# 08_USB_OTG_POWER.net
KiCad netlist of a schematic drawn in Altium Designer
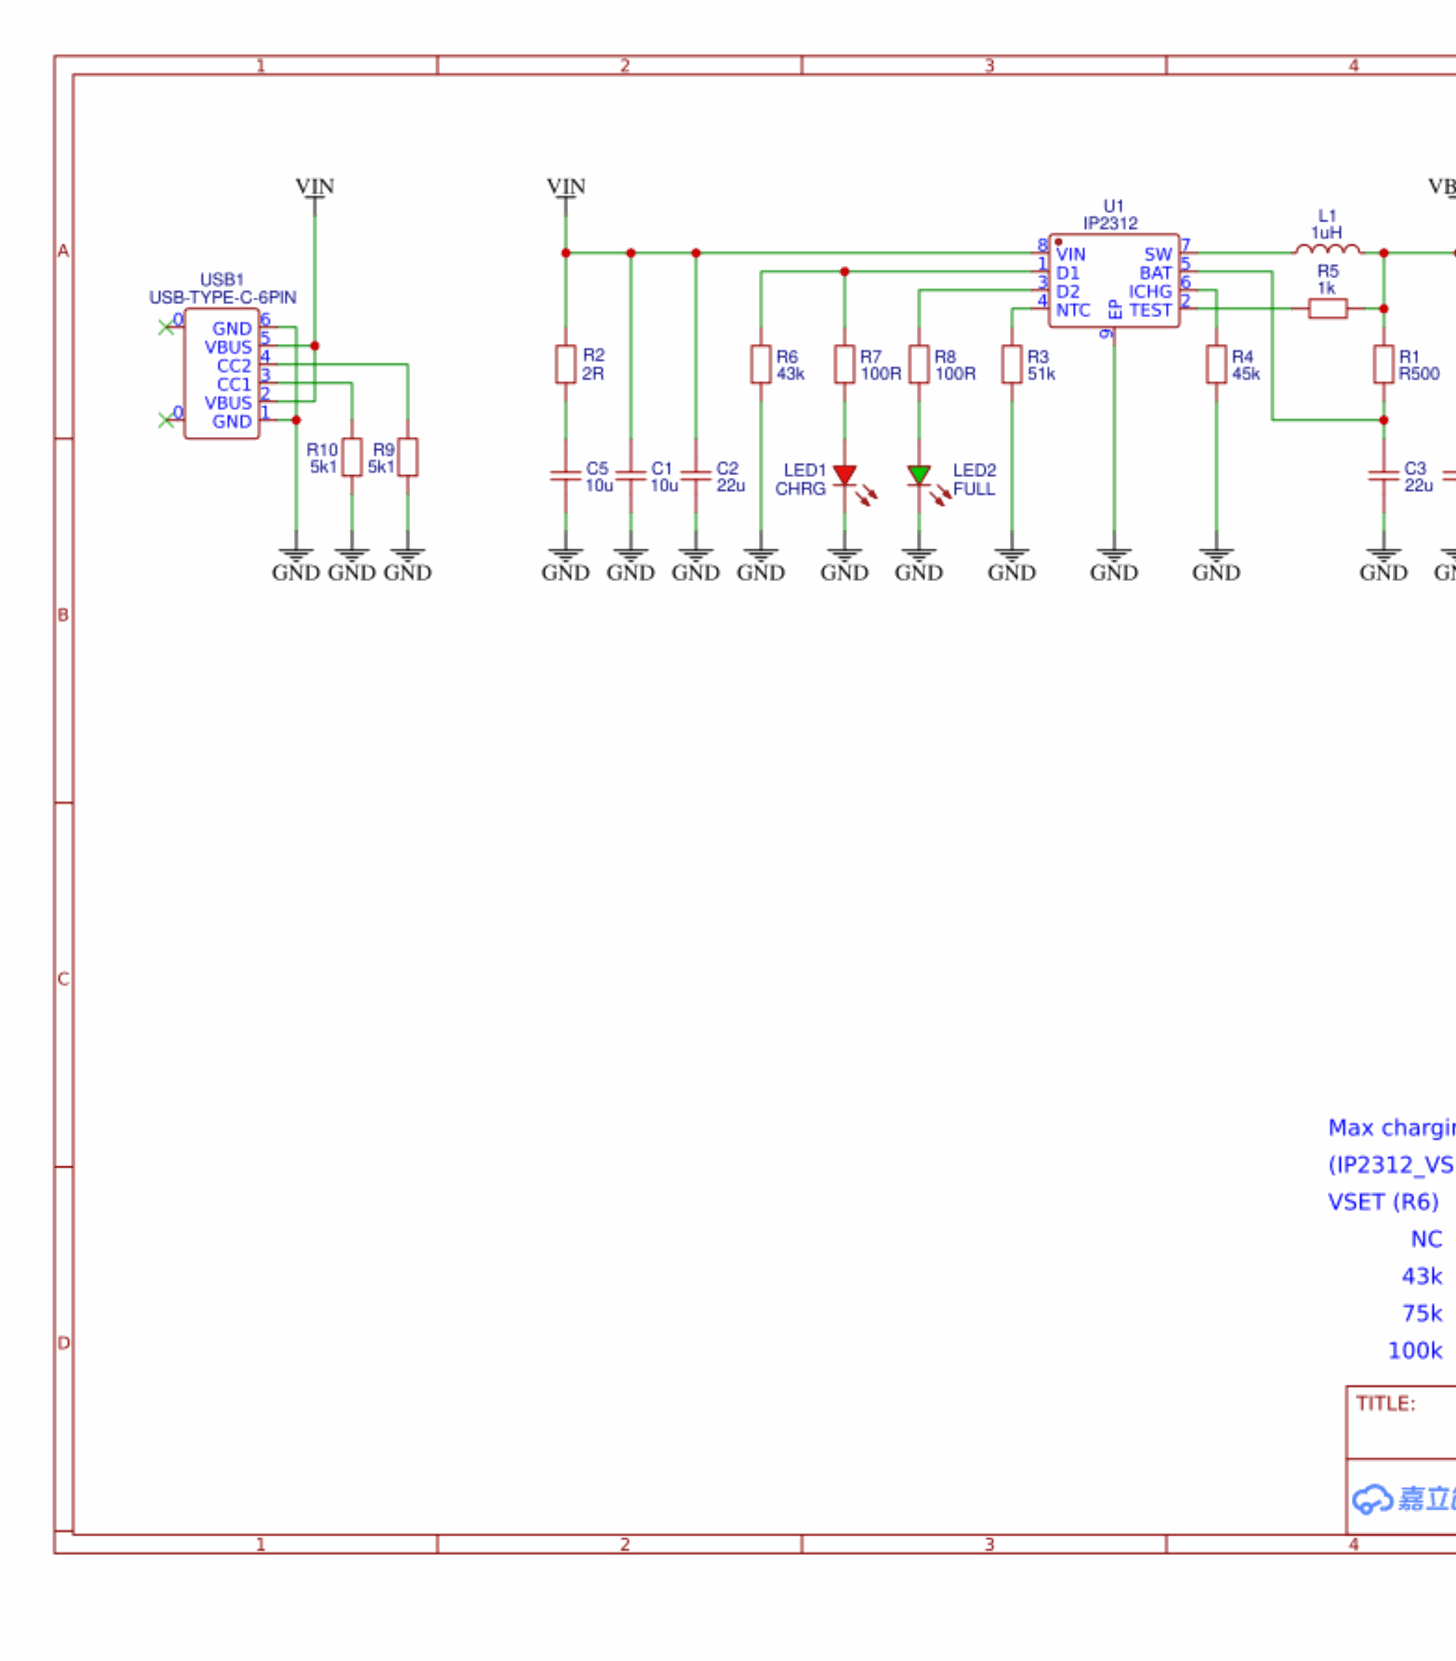
[diagram p0: 08 USB OTG & POWER.SchDoc, left]
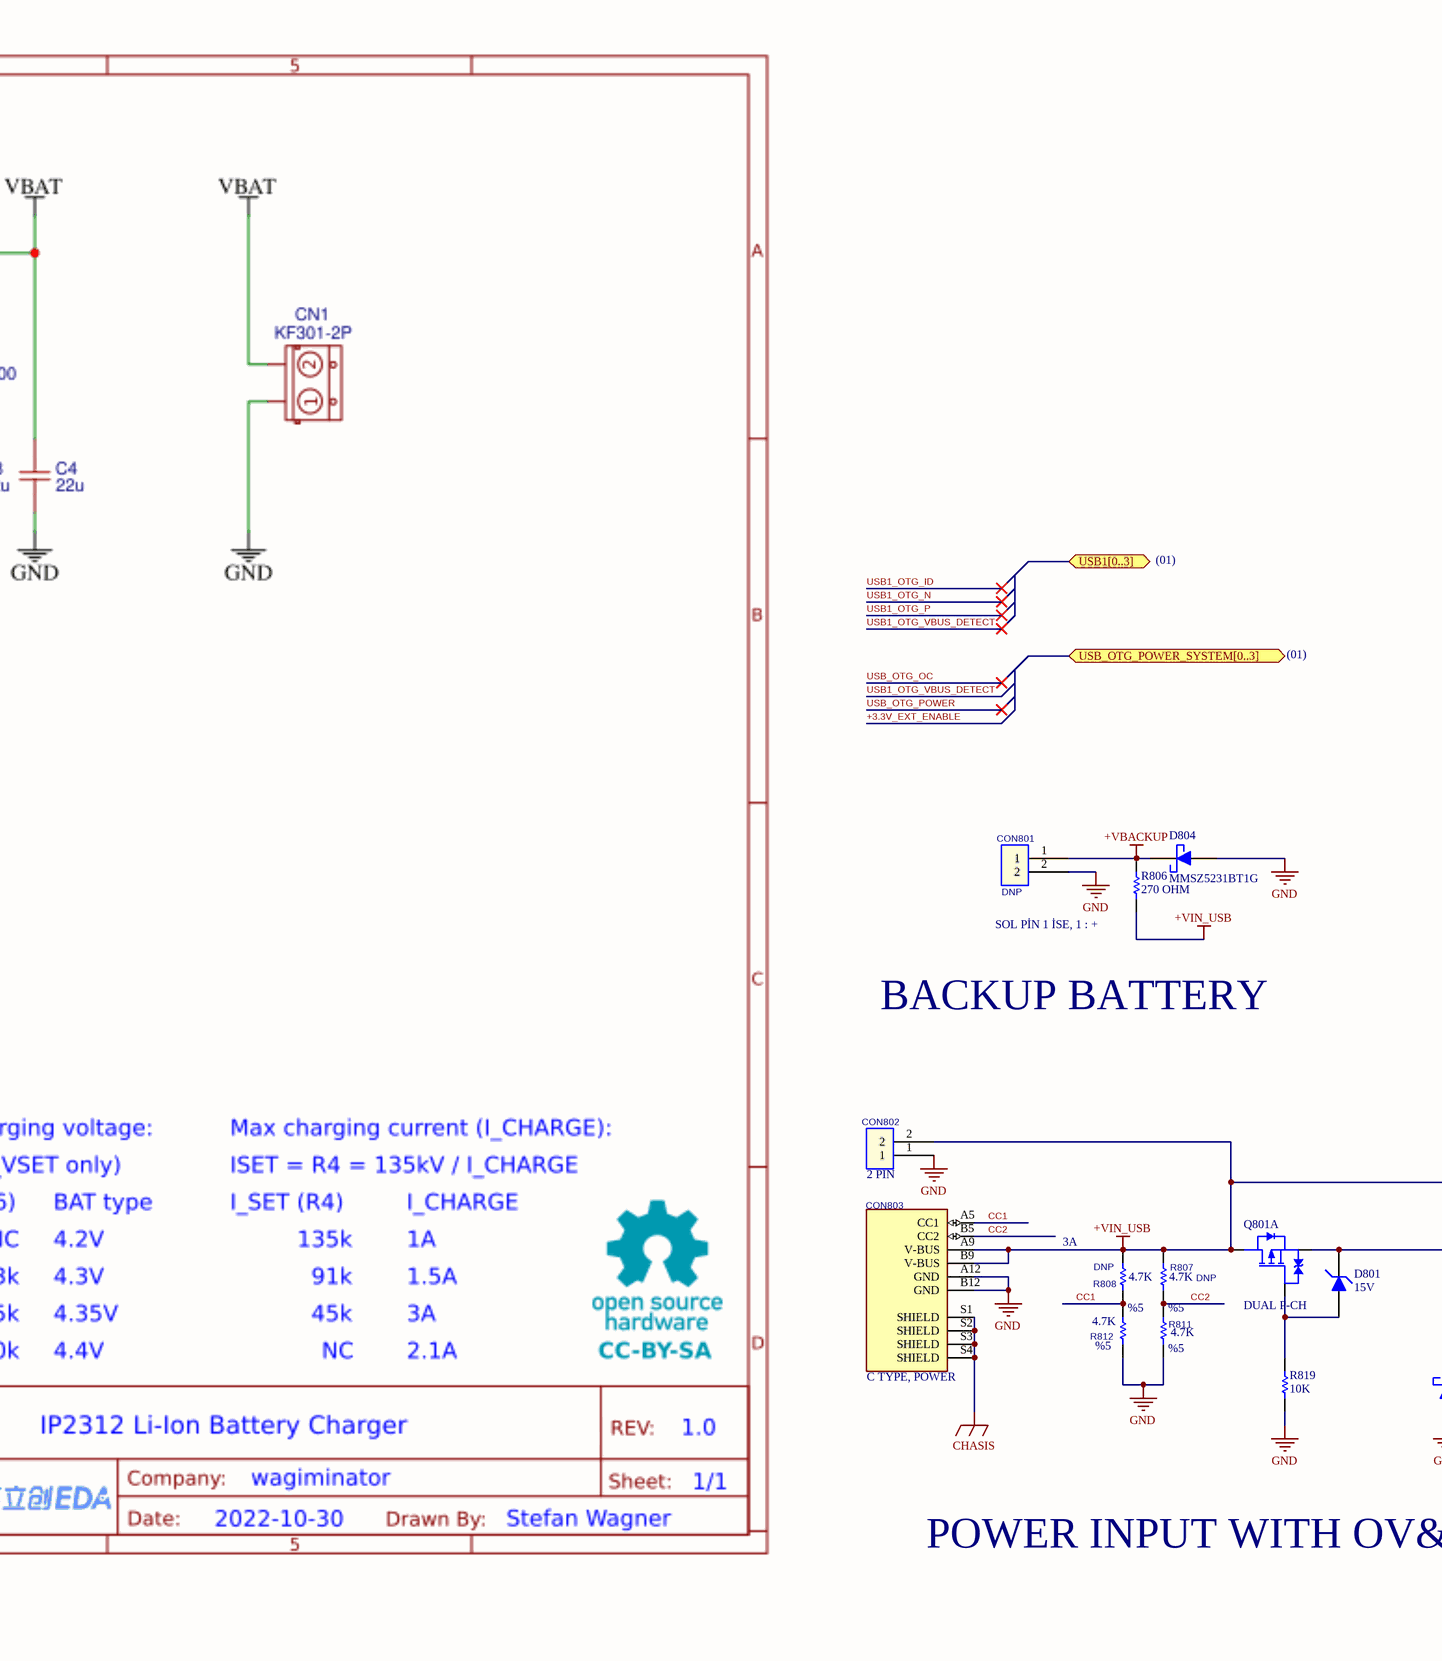
[diagram p1: 08 USB OTG & POWER.SchDoc, middle]
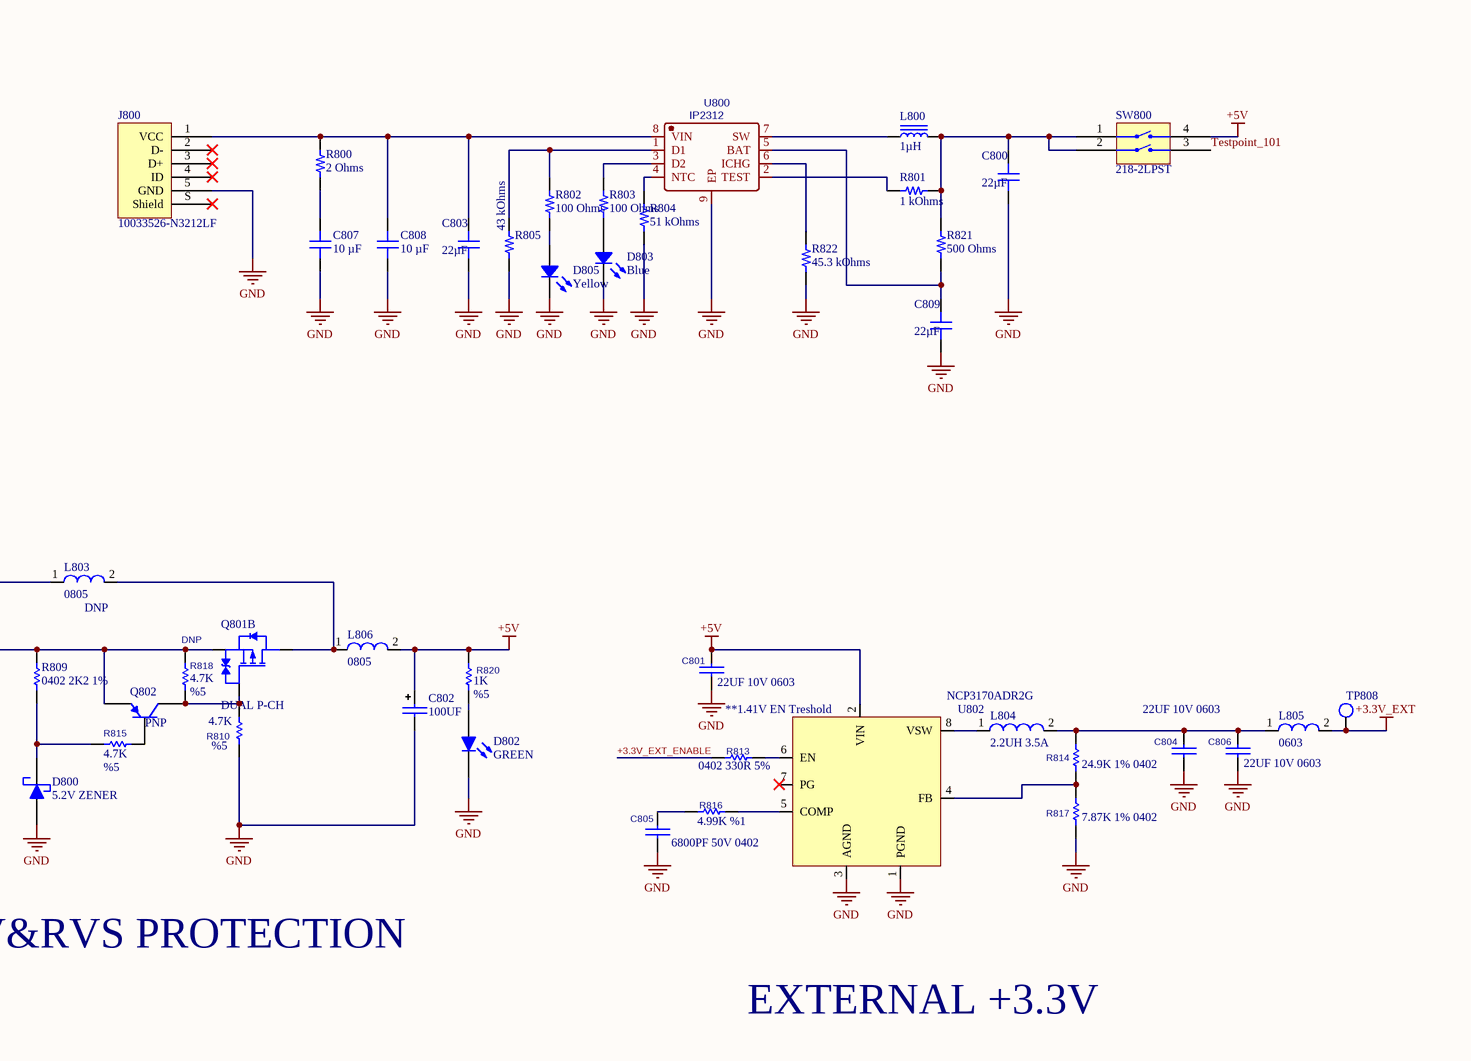
[diagram p2: 08 USB OTG & POWER.SchDoc, right]

(export (version "E")
  (design (tool "Eeschema 10.0.6"))
  (components
    (comp (ref "C800")
      (value "22µF")
      (footprint "CAP 0603_1608")
      (description "CAP CER 22UF 6.3V X5R 0603")
      (fields (field (name "PART NUMBER") "06036D226MAT2A") (field (name "MANUFACTURER") "AVX Corporation"))
      (libsource (lib "Celestial Altium Library - altium_library") (part "Capacitor"))
    )
    (comp (ref "C801")
      (value "22UF 10V 0603")
      (footprint "0603_CC")
      (description "±20% 10V Ceramic Capacitor X5R 0603 (1608 Metric)")
      (fields (field (name "CREATED BY") "E.E") (field (name "CHECKED BY") "*"))
      (libsource (lib "ARETE_SCH") (part "CAP-C1608X5R1A226M080AC"))
    )
    (comp (ref "C802")
      (value "100UF")
      (footprint "UWR1A101MCL1GB")
      (description "CAP ALUM 100UF 20% 10V SMD")
      (fields (field (name "CREATED BY") "EE") (field (name "CHECKED BY") "*"))
      (libsource (lib "ARETE_V2_SCH") (part "CAP-UWR1A101MCL1GB"))
    )
    (comp (ref "C803")
      (value "22µF")
      (footprint "CAP 0603_1608")
      (description "CAP CER 22UF 6.3V X5R 0603")
      (fields (field (name "PART NUMBER") "06036D226MAT2A") (field (name "MANUFACTURER") "AVX Corporation"))
      (libsource (lib "Celestial Altium Library - altium_library") (part "Capacitor"))
    )
    (comp (ref "C804")
      (value "22UF 10V 0603")
      (footprint "0603_CC")
      (description "±20% 10V Ceramic Capacitor X5R 0603 (1608 Metric)")
      (fields (field (name "CREATED BY") "E.E") (field (name "CHECKED BY") "*"))
      (libsource (lib "ARETE_SCH") (part "CAP-C1608X5R1A226M080AC"))
    )
    (comp (ref "C805")
      (value "6800PF 50V 0402")
      (footprint "0402_CC")
      (description "6800pF ±10% 50V Ceramic Capacitor X7R 0402 (1005 Metric)")
      (fields (field (name "CREATED BY") "E.E") (field (name "CHECKED BY") "*"))
      (libsource (lib "ARETE_SCH") (part "CAP-CL05B682KB5NNNC"))
    )
    (comp (ref "C806")
      (value "22UF 10V 0603")
      (footprint "0603_CC")
      (description "±20% 10V Ceramic Capacitor X5R 0603 (1608 Metric)")
      (fields (field (name "CREATED BY") "E.E") (field (name "CHECKED BY") "*"))
      (libsource (lib "ARETE_SCH") (part "CAP-C1608X5R1A226M080AC"))
    )
    (comp (ref "C807")
      (value "10 µF")
      (footprint "CAP 0603_1608")
      (description "CAP CER 10UF 4V X5R 0603")
      (fields
        (field (name "PART NUMBER") "GRM188R60G106ME47D")
        (field (name "MANUFACTURER") "Murata Electronics")
      )
      (libsource (lib "Celestial Altium Library - altium_library") (part "Capacitor"))
    )
    (comp (ref "C808")
      (value "10 µF")
      (footprint "CAP 0603_1608")
      (description "CAP CER 10UF 4V X5R 0603")
      (fields
        (field (name "PART NUMBER") "GRM188R60G106ME47D")
        (field (name "MANUFACTURER") "Murata Electronics")
      )
      (libsource (lib "Celestial Altium Library - altium_library") (part "Capacitor"))
    )
    (comp (ref "C809")
      (value "22µF")
      (footprint "CAP 0603_1608")
      (description "CAP CER 22UF 6.3V X5R 0603")
      (fields (field (name "PART NUMBER") "06036D226MAT2A") (field (name "MANUFACTURER") "AVX Corporation"))
      (libsource (lib "Celestial Altium Library - altium_library") (part "Capacitor"))
    )
    (comp (ref "CON801")
      (value "CON-B2B-PH-K-S(LF)(SN)")
      (footprint "B2B-PH-K-S")
      (description "CONN HEADER VERT 2POS 2MM")
      (fields
        (field (name "ASSY_OPT") "DNP")
        (field (name "CREATED BY") "LA")
        (field (name "CHECKED BY") "*")
      )
      (libsource (lib "ARETE_L") (part "CON-B2B-PH-K-S(LF)(SN)"))
    )
    (comp (ref "CON802")
      (value "2 PIN")
      (footprint "640456-2")
      (description "CONN HEADER VERT 2POS 2.54MM")
      (fields (field (name "CREATED BY") "LA") (field (name "CHECKED BY") "*"))
      (libsource (lib "ARETE_L") (part "CON-640456-2"))
    )
    (comp (ref "CON803")
      (value "C TYPE, POWER")
      (footprint "CUI_UJC-HP-3-SMT-TR")
      (description "USB JACK, C TYPE, POWER ONLY, 6")
      (fields (field (name "CREATED BY") "E.E") (field (name "CHECKED BY") "*"))
      (libsource (lib "ARETE_SCH") (part "0-CON-UJC-HP-3-SMT-TR"))
    )
    (comp (ref "D800")
      (value "5.2V ZENER")
      (footprint "SOD-323")
      (description "DIODE ZENER 5.1V 320MW SOD323")
      (fields (field (name "CREATED BY") "EE") (field (name "CHECKED BY") "*"))
      (libsource (lib "ARETE_V2_SCH") (part "DIODE-PZU5.1B2A,115"))
    )
    (comp (ref "D801")
      (value "15V")
      (footprint "SOD-323")
      (description "DIODE ZENER 15V 400MW SOD323")
      (fields (field (name "CREATED BY") "LA") (field (name "CHECKED BY") "*"))
      (libsource (lib "ARETE_V2_SCH") (part "DIODE-PDZ15B,115"))
    )
    (comp (ref "D802")
      (value "GREEN")
      (footprint "0603_LED")
      (description "LED SMD 0603 SUPER GREEN")
      (fields (field (name "CREATED BY") "*") (field (name "CHECKED BY") "*"))
      (libsource (lib "ARETE_SCH") (part "LED-LTST-C190KRKT"))
    )
    (comp (ref "D803")
      (value "Blue")
      (footprint "LED 0603_1608 BLUE")
      (description "LED BLUE DIFFUSED 0603 SMD")
      (fields
        (field (name "PART NUMBER") "LB Q39E-N1OO-35-1")
        (field (name "MANUFACTURER") "OSRAM Opto Semiconductors Inc.")
      )
      (libsource (lib "Celestial Altium Library - altium_library") (part "LED"))
    )
    (comp (ref "D804")
      (value "MMSZ5231BT1G")
      (footprint "SOD-123")
      (description "DIODE ZENER 5.1V 500MW SOD123")
      (fields (field (name "CREATED BY") "EE") (field (name "CHECKED BY") "*"))
      (libsource (lib "ARETE_SCH") (part "DIODE-MMSZ5231BT1G"))
    )
    (comp (ref "D805")
      (value "Yellow")
      (footprint "LED 0603_1608 YELLOW")
      (description "LED YELLOW 1608 SMD")
      (fields (field (name "PART NUMBER") "SML-D15YWT86C") (field (name "MANUFACTURER") "Rohm Semiconductor"))
      (libsource (lib "Celestial Altium Library - altium_library") (part "LED"))
    )
    (comp (ref "J800")
      (value "10033526-N3212LF")
      (footprint "FCI USB 10033526-N3212LF")
      (description "CONN RCPT MINI USB B 5POS SMD RA")
      (fields (field (name "MANUFACTURER") "Amphenol ICC (FCI)"))
      (libsource (lib "Celestial Altium Library - altium_library") (part "USB 2.0 Type B Micro"))
    )
    (comp (ref "L800")
      (value "1µH")
      (footprint "IND 0603_1608 RF WW")
      (description "FIXED IND 1UH 280MA 940 MOHM SMD")
      (fields (field (name "PART NUMBER") "AISC-0603F-1R0J-T") (field (name "MANUFACTURER") "Abracon LLC"))
      (libsource (lib "Celestial Altium Library - altium_library") (part "Inductor"))
    )
    (comp (ref "L803")
      (value "0805")
      (footprint "0805")
      (description "0OHM 0805")
      (fields
        (field (name "ASSY_OPT") "DNP")
        (field (name "CREATED BY") "EE")
        (field (name "CHECKED BY") "*")
      )
      (libsource (lib "ARETE_V2_SCH") (part "IND-FERRITE (RES 0 OHM) 0805"))
    )
    (comp (ref "L804")
      (value "2.2UH 3.5A")
      (footprint "IND-NRS5030T2R2NMGJ")
      (description "Shielded Wirewound Inductor 23mOhm Nonstandard")
      (fields (field (name "CREATED BY") "E.E") (field (name "CHECKED BY") "*"))
      (libsource (lib "ARETE_SCH") (part "IND-NRS5030T2R2NMGJ"))
    )
    (comp (ref "L805")
      (value "0603")
      (footprint "0603_RES")
      (description "0OHM 0603")
      (fields (field (name "CREATED BY") "EE") (field (name "CHECKED BY") "*"))
      (libsource (lib "ARETE_SCH") (part "IND-FERRITE (RES 0 OHM) 0603"))
    )
    (comp (ref "L806")
      (value "0805")
      (footprint "0805")
      (description "0OHM 0805")
      (fields (field (name "CREATED BY") "EE") (field (name "CHECKED BY") "*"))
      (libsource (lib "ARETE_V2_SCH") (part "IND-FERRITE (RES 0 OHM) 0805"))
    )
    (comp (ref "Q801")
      (value "DUAL P-CH")
      (footprint "SO-8 - DUAL MOS - NAMED")
      (description "MOSFET 2P-CH 30V 6A SO-8")
      (fields (field (name "CREATED BY") "*") (field (name "CHECKED BY") "*"))
      (libsource (lib "ARETE_V2_SCH") (part "MOS-P-DMP3028LSD-13"))
    )
    (comp (ref "Q802")
      (value "PNP")
      (footprint "SOT23")
      (description "TRANS PNP 65V 0.1A SOT-23")
      (fields (field (name "CREATED BY") "LA") (field (name "CHECKED BY") "*"))
      (libsource (lib "ARETE_V2_SCH") (part "TRANSISTOR-BC856"))
    )
    (comp (ref "R800")
      (value "2 Ohms")
      (footprint "RES 0603_1608")
      (description "RES 2 OHM 5% 1/8W 0603")
      (fields
        (field (name "PART NUMBER") "RK73B1JTTD2R0J")
        (field (name "MANUFACTURER") "KOA Speer Electronics, Inc.")
      )
      (libsource (lib "Celestial Altium Library - altium_library") (part "Resistor"))
    )
    (comp (ref "R801")
      (value "1 kOhms")
      (footprint "RES 0603_1608")
      (description "RES SMD 1K OHM 0.1% 1/16W 0603")
      (fields
        (field (name "PART NUMBER") "CPF0603B1K0E")
        (field (name "MANUFACTURER") "TE Connectivity Passive Product")
      )
      (libsource (lib "Celestial Altium Library - altium_library") (part "Resistor"))
    )
    (comp (ref "R802")
      (value "100 Ohms")
      (footprint "RES 0603_1608")
      (description "RES 100 OHM 0.1% 1/16W 0603")
      (fields
        (field (name "PART NUMBER") "RNCS0603BKE100R")
        (field (name "MANUFACTURER") "Stackpole Electronics Inc")
      )
      (libsource (lib "Celestial Altium Library - altium_library") (part "Resistor"))
    )
    (comp (ref "R803")
      (value "100 Ohms")
      (footprint "RES 0603_1608")
      (description "RES 100 OHM 0.1% 1/16W 0603")
      (fields
        (field (name "PART NUMBER") "RNCS0603BKE100R")
        (field (name "MANUFACTURER") "Stackpole Electronics Inc")
      )
      (libsource (lib "Celestial Altium Library - altium_library") (part "Resistor"))
    )
    (comp (ref "R804")
      (value "51 kOhms")
      (footprint "RES 0603_1608")
      (description "RES 51K OHM 5% 1/10W 0603")
      (fields
        (field (name "PART NUMBER") "RMCF0603JT51K0")
        (field (name "MANUFACTURER") "Stackpole Electronics Inc")
      )
      (libsource (lib "Celestial Altium Library - altium_library") (part "Resistor"))
    )
    (comp (ref "R805")
      (value "43 kOhms")
      (footprint "RES 0603_1608")
      (description "RES SMD 43K OHM 0.1% 1/10W 0603")
      (fields (field (name "PART NUMBER") "RG1608P-433-B-T5") (field (name "MANUFACTURER") "Susumu"))
      (libsource (lib "Celestial Altium Library - altium_library") (part "Resistor"))
    )
    (comp (ref "R806")
      (value "270 OHM")
      (footprint "0603_RES")
      (description "RES SMD 270 OHM 5% 1/10W 0603")
      (fields (field (name "CREATED BY") "EE") (field (name "CHECKED BY") "*"))
      (libsource (lib "ARETE_SCH") (part "RES-RC0603JR-07270RL"))
    )
    (comp (ref "R807")
      (value "4.7K")
      (footprint "0402_RES")
      (description "RES 4.7K OHM 5% 1/16W 0402")
      (fields
        (field (name "ASSY_OPT") "DNP")
        (field (name "TOLERANCE") "%5")
        (field (name "CREATED BY") "LA")
        (field (name "CHECKED BY") "*")
      )
      (libsource (lib "ARETE_SCH") (part "RES-4.7K"))
    )
    (comp (ref "R808")
      (value "4.7K")
      (footprint "0402_RES")
      (description "RES 4.7K OHM 5% 1/16W 0402")
      (fields
        (field (name "ASSY_OPT") "DNP")
        (field (name "TOLERANCE") "%5")
        (field (name "CREATED BY") "LA")
        (field (name "CHECKED BY") "*")
      )
      (libsource (lib "ARETE_SCH") (part "RES-4.7K"))
    )
    (comp (ref "R809")
      (value "0402 2K2 1%")
      (footprint "0402_RES")
      (fields (field (name "CREATED BY") "E.E") (field (name "CHECKED BY") "*"))
      (libsource (lib "ARETE_V2_SCH") (part "RES-CRGCQ0402F2K2"))
    )
    (comp (ref "R810")
      (value "4.7K")
      (footprint "0402_RES")
      (description "RES 4.7K OHM 5% 1/16W 0402")
      (fields
        (field (name "TOLERANCE") "%5")
        (field (name "CREATED BY") "LA")
        (field (name "CHECKED BY") "*")
      )
      (libsource (lib "ARETE_SCH") (part "RES-4.7K"))
    )
    (comp (ref "R811")
      (value "4.7K")
      (footprint "0402_RES")
      (description "RES 4.7K OHM 5% 1/16W 0402")
      (fields
        (field (name "TOLERANCE") "%5")
        (field (name "CREATED BY") "LA")
        (field (name "CHECKED BY") "*")
      )
      (libsource (lib "ARETE_SCH") (part "RES-4.7K"))
    )
    (comp (ref "R812")
      (value "4.7K")
      (footprint "0402_RES")
      (description "RES 4.7K OHM 5% 1/16W 0402")
      (fields
        (field (name "TOLERANCE") "%5")
        (field (name "CREATED BY") "LA")
        (field (name "CHECKED BY") "*")
      )
      (libsource (lib "ARETE_SCH") (part "RES-4.7K"))
    )
    (comp (ref "R813")
      (value "0402 330R 5%")
      (footprint "0402_RES")
      (fields
        (field (name "TOLERANCE") "%5")
        (field (name "CREATED BY") "E.E")
        (field (name "CHECKED BY") "*")
      )
      (libsource (lib "ARETE_SCH") (part "RES-CRGCQ0402J330R"))
    )
    (comp (ref "R814")
      (value "24.9K 1% 0402")
      (footprint "0402_RES")
      (description "24.9 ±1% 0.063W, 1/16W Chip Resistor 0402 (1005 Metric) - Thick Film")
      (fields (field (name "CREATED BY") "E.E") (field (name "CHECKED BY") "*"))
      (libsource (lib "ARETE_SCH") (part "RES-RC0402FR-0724K9L"))
    )
    (comp (ref "R815")
      (value "4.7K")
      (footprint "0402_RES")
      (description "RES 4.7K OHM 5% 1/16W 0402")
      (fields
        (field (name "TOLERANCE") "%5")
        (field (name "CREATED BY") "LA")
        (field (name "CHECKED BY") "*")
      )
      (libsource (lib "ARETE_SCH") (part "RES-4.7K"))
    )
    (comp (ref "R816")
      (value "4.99K %1")
      (footprint "0603_RES")
      (description "RES 4.99K OHM %1 1/10W 0603")
      (fields (field (name "CREATED BY") "LA") (field (name "CHECKED BY") "*"))
      (libsource (lib "ARETE_SCH") (part "RES-RC0603FR-074K99L"))
    )
    (comp (ref "R817")
      (value "7.87K 1% 0402")
      (footprint "0402_RES")
      (description "7.87 kOhms ±1% 0.063W, 1/16W Chip Resistor 0402 (1005 Metric) Automotive AEC-Q200 Thick Film")
      (fields (field (name "CREATED BY") "EE") (field (name "CHECKED BY") "*"))
      (libsource (lib "ARETE_SCH") (part "RES-CRCW04027K87FKED"))
    )
    (comp (ref "R818")
      (value "4.7K")
      (footprint "0402_RES")
      (description "RES 4.7K OHM 5% 1/16W 0402")
      (fields
        (field (name "ASSY_OPT") "DNP")
        (field (name "TOLERANCE") "%5")
        (field (name "CREATED BY") "LA")
        (field (name "CHECKED BY") "*")
      )
      (libsource (lib "ARETE_SCH") (part "RES-4.7K"))
    )
    (comp (ref "R819")
      (value "10K")
      (footprint "0805")
      (description "RES SMD 10K 5% 0805")
      (fields (field (name "CREATED BY") "*") (field (name "CHECKED BY") "*"))
      (libsource (lib "ARETE_V2_SCH") (part "RES-0805S8J0103TDE"))
    )
    (comp (ref "R820")
      (value "1K")
      (footprint "0402_RES")
      (description "RES 1K OHM 5% 1/16W 0402")
      (fields
        (field (name "TOLERANCE") "%5")
        (field (name "CREATED BY") "LA")
        (field (name "CHECKED BY") "*")
      )
      (libsource (lib "ARETE_SCH") (part "RES-RMCF0402JT1K00"))
    )
    (comp (ref "R821")
      (value "500 Ohms")
      (footprint "RES 0603_1608")
      (description "RES SMD 500 OHM 0.05% 1/10W 0603")
      (fields (field (name "PART NUMBER") "TNPU0603500RAZEN00") (field (name "MANUFACTURER") "Vishay Dale"))
      (libsource (lib "Celestial Altium Library - altium_library") (part "Resistor"))
    )
    (comp (ref "R822")
      (value "45.3 kOhms")
      (footprint "RES 0603_1608")
      (description "RES SMD 45.3K OHM 1% 1/16W 0603")
      (fields
        (field (name "PART NUMBER") "CPF0603F45K3C1")
        (field (name "MANUFACTURER") "TE Connectivity Passive Product")
      )
      (libsource (lib "Celestial Altium Library - altium_library") (part "Resistor"))
    )
    (comp (ref "SW800")
      (value "218-2LPST")
      (footprint "CTS 218-2LPJ")
      (description "SWITCH SLIDE DIP SPST 25MA 24V")
      (fields (field (name "MANUFACTURER") "CTS Electrocomponents"))
      (libsource (lib "Celestial Altium Library - altium_library") (part "DIP SW 2P"))
    )
    (comp (ref "TP808")
      (value "TEST POINT 35")
      (footprint "testpoint_35mil")
      (libsource (lib "ARETE_SCH") (part "TEST POINT 35"))
    )
    (comp (ref "U800")
      (value "IP2312")
      (footprint "SOP-8_EP_150MIL")
      (fields
        (field (name "MANUFACTURER") "INJOINIC(英集芯)")
        (field (name "MANUFACTURER PART") "IP2312U_VSET")
        (field (name "CONTRIBUTOR") "Stefan Wagner")
      )
      (libsource (lib "altium-import") (part "root_0_IP2312_"))
    )
    (comp (ref "U802")
      (value "NCP3170ADR2G")
      (footprint "IC-NCP3170ADR2G")
      (description "Buck Regulator, Switching, PWM, 3.0 A")
      (fields (field (name "CREATED BY") "E.E") (field (name "CHECKED BY") "*"))
      (libsource (lib "ARETE_SCH") (part "IC-NCP3170ADR2G"))
    )
  )
  (nets
    (net (code "9") (name "+3.3V_EXT") (class "Default")
      (node (ref "L805") (pin "2") (pinfunction "2_2") (pintype "passive"))
      (node (ref "TP808") (pin "1") (pinfunction "1_1") (pintype "passive"))
    )
    (net (code "10") (name "+5V") (class "Default")
      (node (ref "C801") (pin "1") (pinfunction "1_1") (pintype "passive"))
      (node (ref "C802") (pin "1") (pinfunction "1_1") (pintype "passive"))
      (node (ref "L806") (pin "2") (pinfunction "2_2") (pintype "passive"))
      (node (ref "R820") (pin "1") (pinfunction "1_1") (pintype "passive"))
      (node (ref "SW800") (pin "4") (pinfunction "GND_4") (pintype "passive"))
      (node (ref "U802") (pin "2") (pinfunction "VIN_2") (pintype "passive"))
    )
    (net (code "11") (name "+VBACKUP") (class "Default")
      (node (ref "CON801") (pin "1") (pinfunction "1_1") (pintype "passive"))
      (node (ref "D804") (pin "K") (pinfunction "K_K") (pintype "passive"))
      (node (ref "R806") (pin "1") (pinfunction "1_1") (pintype "passive"))
    )
    (net (code "12") (name "+VIN_USB") (class "Default")
      (node (ref "CON802") (pin "2") (pinfunction "2_2") (pintype "passive"))
      (node (ref "CON803") (pin "A9") (pinfunction "V-BUS_A9") (pintype "power_in"))
      (node (ref "CON803") (pin "B9") (pinfunction "V-BUS_B9") (pintype "power_in"))
      (node (ref "L803") (pin "1") (pinfunction "1_1") (pintype "passive"))
      (node (ref "Q801") (pin "D1") (pinfunction "D1_D1") (pintype "passive"))
      (node (ref "R806") (pin "2") (pinfunction "2_2") (pintype "passive"))
      (node (ref "R807") (pin "1") (pinfunction "1_1") (pintype "passive"))
      (node (ref "R808") (pin "1") (pinfunction "1_1") (pintype "passive"))
    )
    (net (code "13") (name "/+3.3V_EXT_ENABLE") (class "Default")
      (node (ref "R813") (pin "1") (pinfunction "1_1") (pintype "passive"))
    )
    (net (code "14") (name "/CC1") (class "Default")
      (node (ref "CON803") (pin "A5") (pinfunction "CC1_A5") (pintype "bidirectional"))
      (node (ref "R808") (pin "2") (pinfunction "2_2") (pintype "passive"))
      (node (ref "R812") (pin "1") (pinfunction "1_1") (pintype "passive"))
    )
    (net (code "15") (name "/CC2") (class "Default")
      (node (ref "CON803") (pin "B5") (pinfunction "CC2_B5") (pintype "bidirectional"))
      (node (ref "R807") (pin "2") (pinfunction "2_2") (pintype "passive"))
      (node (ref "R811") (pin "1") (pinfunction "1_1") (pintype "passive"))
    )
    (net (code "16") (name "/Testpoint_101") (class "Default")
      (node (ref "SW800") (pin "3") (pinfunction "GND_3") (pintype "passive"))
    )
    (net (code "25") (name "CHASIS") (class "Default")
      (node (ref "CON803") (pin "S1") (pinfunction "SHIELD_S1") (pintype "passive"))
      (node (ref "CON803") (pin "S2") (pinfunction "SHIELD_S2") (pintype "passive"))
      (node (ref "CON803") (pin "S3") (pinfunction "SHIELD_S3") (pintype "passive"))
      (node (ref "CON803") (pin "S4") (pinfunction "SHIELD_S4") (pintype "passive"))
    )
    (net (code "26") (name "GND") (class "Default")
      (node (ref "C800") (pin "1") (pinfunction "1_1") (pintype "passive"))
      (node (ref "C801") (pin "2") (pinfunction "2_2") (pintype "passive"))
      (node (ref "C802") (pin "2") (pinfunction "2_2") (pintype "passive"))
      (node (ref "C803") (pin "1") (pinfunction "1_1") (pintype "passive"))
      (node (ref "C804") (pin "2") (pinfunction "2_2") (pintype "passive"))
      (node (ref "C805") (pin "2") (pinfunction "2_2") (pintype "passive"))
      (node (ref "C806") (pin "2") (pinfunction "2_2") (pintype "passive"))
      (node (ref "C807") (pin "1") (pinfunction "1_1") (pintype "passive"))
      (node (ref "C808") (pin "1") (pinfunction "1_1") (pintype "passive"))
      (node (ref "C809") (pin "1") (pinfunction "1_1") (pintype "passive"))
      (node (ref "CON801") (pin "2") (pinfunction "2_2") (pintype "passive"))
      (node (ref "CON802") (pin "1") (pinfunction "1_1") (pintype "passive"))
      (node (ref "CON803") (pin "A12") (pinfunction "GND_A12") (pintype "power_in"))
      (node (ref "CON803") (pin "B12") (pinfunction "GND_B12") (pintype "power_in"))
      (node (ref "D800") (pin "A") (pinfunction "A_A") (pintype "passive"))
      (node (ref "D802") (pin "2") (pinfunction "K_2") (pintype "passive"))
      (node (ref "D803") (pin "2") (pinfunction "2_2") (pintype "passive"))
      (node (ref "D804") (pin "A") (pinfunction "A_A") (pintype "passive"))
      (node (ref "D805") (pin "2") (pinfunction "2_2") (pintype "passive"))
      (node (ref "J800") (pin "5") (pinfunction "GND_5") (pintype "passive"))
      (node (ref "R804") (pin "1") (pinfunction "1_1") (pintype "passive"))
      (node (ref "R805") (pin "1") (pinfunction "1_1") (pintype "passive"))
      (node (ref "R810") (pin "2") (pinfunction "2_2") (pintype "passive"))
      (node (ref "R811") (pin "2") (pinfunction "2_2") (pintype "passive"))
      (node (ref "R812") (pin "2") (pinfunction "2_2") (pintype "passive"))
      (node (ref "R817") (pin "1") (pinfunction "1_1") (pintype "passive"))
      (node (ref "R819") (pin "1") (pinfunction "1_1") (pintype "passive"))
      (node (ref "R822") (pin "1") (pinfunction "1_1") (pintype "passive"))
      (node (ref "U800") (pin "9") (pinfunction "EP_9") (pintype "passive"))
      (node (ref "U802") (pin "1") (pinfunction "PGND_1") (pintype "passive"))
      (node (ref "U802") (pin "3") (pinfunction "AGND_3") (pintype "passive"))
    )
    (net (code "27") (name "Net-(C800-Pad2)") (class "Default")
      (node (ref "C800") (pin "2") (pinfunction "2_2") (pintype "passive"))
      (node (ref "L800") (pin "2") (pinfunction "2_2") (pintype "passive"))
      (node (ref "R801") (pin "2") (pinfunction "2_2") (pintype "passive"))
      (node (ref "R821") (pin "2") (pinfunction "2_2") (pintype "passive"))
      (node (ref "SW800") (pin "1") (pinfunction "GND_1") (pintype "passive"))
      (node (ref "SW800") (pin "2") (pinfunction "GND_2") (pintype "passive"))
    )
    (net (code "28") (name "Net-(C804-Pad1)") (class "Default")
      (node (ref "C804") (pin "1") (pinfunction "1_1") (pintype "passive"))
      (node (ref "C806") (pin "1") (pinfunction "1_1") (pintype "passive"))
      (node (ref "L804") (pin "2") (pinfunction "2_2") (pintype "passive"))
      (node (ref "L805") (pin "1") (pinfunction "1_1") (pintype "passive"))
      (node (ref "R814") (pin "2") (pinfunction "2_2") (pintype "passive"))
    )
    (net (code "29") (name "Net-(C805-Pad1)") (class "Default")
      (node (ref "C805") (pin "1") (pinfunction "1_1") (pintype "passive"))
      (node (ref "R816") (pin "1") (pinfunction "1_1") (pintype "passive"))
    )
    (net (code "30") (name "Net-(C807-Pad2)") (class "Default")
      (node (ref "C807") (pin "2") (pinfunction "2_2") (pintype "passive"))
      (node (ref "R800") (pin "1") (pinfunction "1_1") (pintype "passive"))
    )
    (net (code "31") (name "Net-(D800-PadK)") (class "Default")
      (node (ref "D800") (pin "K") (pinfunction "K_K") (pintype "passive"))
      (node (ref "R809") (pin "1") (pinfunction "1_1") (pintype "passive"))
      (node (ref "R815") (pin "1") (pinfunction "1_1") (pintype "passive"))
    )
    (net (code "32") (name "Net-(D801-PadA)") (class "Default")
      (node (ref "D801") (pin "A") (pinfunction "A_A") (pintype "passive"))
      (node (ref "Q801") (pin "G1") (pinfunction "G1_G1") (pintype "passive"))
      (node (ref "R819") (pin "2") (pinfunction "2_2") (pintype "passive"))
    )
    (net (code "33") (name "Net-(D802-A)") (class "Default")
      (node (ref "D802") (pin "1") (pinfunction "A_1") (pintype "passive"))
      (node (ref "R820") (pin "2") (pinfunction "2_2") (pintype "passive"))
    )
    (net (code "34") (name "Net-(D803-Pad1)") (class "Default")
      (node (ref "D803") (pin "1") (pinfunction "1_1") (pintype "passive"))
      (node (ref "R803") (pin "1") (pinfunction "1_1") (pintype "passive"))
    )
    (net (code "35") (name "Net-(D805-Pad1)") (class "Default")
      (node (ref "D805") (pin "1") (pinfunction "1_1") (pintype "passive"))
      (node (ref "R802") (pin "1") (pinfunction "1_1") (pintype "passive"))
    )
    (net (code "36") (name "Net-(J800-VCC)") (class "Default")
      (node (ref "C803") (pin "2") (pinfunction "2_2") (pintype "passive"))
      (node (ref "C808") (pin "2") (pinfunction "2_2") (pintype "passive"))
      (node (ref "J800") (pin "1") (pinfunction "VCC_1") (pintype "passive"))
      (node (ref "R800") (pin "2") (pinfunction "2_2") (pintype "passive"))
      (node (ref "U800") (pin "8") (pinfunction "VIN_8") (pintype "passive"))
    )
    (net (code "37") (name "Net-(L803-Pad2)") (class "Default")
      (node (ref "L803") (pin "2") (pinfunction "2_2") (pintype "passive"))
      (node (ref "L806") (pin "1") (pinfunction "1_1") (pintype "passive"))
      (node (ref "Q801") (pin "D2") (pinfunction "D2_D2") (pintype "passive"))
    )
    (net (code "38") (name "Net-(Q802-B)") (class "Default")
      (node (ref "Q802") (pin "1") (pinfunction "B_1") (pintype "passive"))
      (node (ref "R815") (pin "2") (pinfunction "2_2") (pintype "passive"))
    )
    (net (code "39") (name "Net-(Q802-C)") (class "Default")
      (node (ref "Q801") (pin "G2") (pinfunction "G2_G2") (pintype "passive"))
      (node (ref "Q802") (pin "3") (pinfunction "C_3") (pintype "passive"))
      (node (ref "R810") (pin "1") (pinfunction "1_1") (pintype "passive"))
      (node (ref "R818") (pin "1") (pinfunction "1_1") (pintype "passive"))
    )
    (net (code "40") (name "Net-(Q802-E)") (class "Default")
      (node (ref "D801") (pin "K") (pinfunction "K_K") (pintype "passive"))
      (node (ref "Q801") (pin "S1") (pinfunction "S1_S1") (pintype "passive"))
      (node (ref "Q801") (pin "S2") (pinfunction "S2_S2") (pintype "passive"))
      (node (ref "Q802") (pin "2") (pinfunction "E_2") (pintype "passive"))
      (node (ref "R809") (pin "2") (pinfunction "2_2") (pintype "passive"))
      (node (ref "R818") (pin "2") (pinfunction "2_2") (pintype "passive"))
    )
    (net (code "41") (name "Net-(U800-BAT)") (class "Default")
      (node (ref "C809") (pin "2") (pinfunction "2_2") (pintype "passive"))
      (node (ref "R821") (pin "1") (pinfunction "1_1") (pintype "passive"))
      (node (ref "U800") (pin "5") (pinfunction "BAT_5") (pintype "passive"))
    )
    (net (code "42") (name "Net-(U800-D1)") (class "Default")
      (node (ref "R802") (pin "2") (pinfunction "2_2") (pintype "passive"))
      (node (ref "R805") (pin "2") (pinfunction "2_2") (pintype "passive"))
      (node (ref "U800") (pin "1") (pinfunction "D1_1") (pintype "passive"))
    )
    (net (code "43") (name "Net-(U800-D2)") (class "Default")
      (node (ref "R803") (pin "2") (pinfunction "2_2") (pintype "passive"))
      (node (ref "U800") (pin "3") (pinfunction "D2_3") (pintype "passive"))
    )
    (net (code "44") (name "Net-(U800-ICHG)") (class "Default")
      (node (ref "R822") (pin "2") (pinfunction "2_2") (pintype "passive"))
      (node (ref "U800") (pin "6") (pinfunction "ICHG_6") (pintype "passive"))
    )
    (net (code "45") (name "Net-(U800-NTC)") (class "Default")
      (node (ref "R804") (pin "2") (pinfunction "2_2") (pintype "passive"))
      (node (ref "U800") (pin "4") (pinfunction "NTC_4") (pintype "passive"))
    )
    (net (code "46") (name "Net-(U800-SW)") (class "Default")
      (node (ref "L800") (pin "1") (pinfunction "1_1") (pintype "passive"))
      (node (ref "U800") (pin "7") (pinfunction "SW_7") (pintype "passive"))
    )
    (net (code "47") (name "Net-(U800-TEST)") (class "Default")
      (node (ref "R801") (pin "1") (pinfunction "1_1") (pintype "passive"))
      (node (ref "U800") (pin "2") (pinfunction "TEST_2") (pintype "passive"))
    )
    (net (code "48") (name "Net-(U802-COMP)") (class "Default")
      (node (ref "R816") (pin "2") (pinfunction "2_2") (pintype "passive"))
      (node (ref "U802") (pin "5") (pinfunction "COMP_5") (pintype "passive"))
    )
    (net (code "49") (name "Net-(U802-EN)") (class "Default")
      (node (ref "R813") (pin "2") (pinfunction "2_2") (pintype "passive"))
      (node (ref "U802") (pin "6") (pinfunction "EN_6") (pintype "passive"))
    )
    (net (code "50") (name "Net-(U802-FB)") (class "Default")
      (node (ref "R814") (pin "1") (pinfunction "1_1") (pintype "passive"))
      (node (ref "R817") (pin "2") (pinfunction "2_2") (pintype "passive"))
      (node (ref "U802") (pin "4") (pinfunction "FB_4") (pintype "passive"))
    )
    (net (code "51") (name "Net-(U802-VSW)") (class "Default")
      (node (ref "L804") (pin "1") (pinfunction "1_1") (pintype "passive"))
      (node (ref "U802") (pin "8") (pinfunction "VSW_8") (pintype "passive"))
    )
    (net (code "52") (name "unconnected-(J800-D+-Pad3)") (class "Default")
      (node (ref "J800") (pin "3") (pinfunction "D+_3") (pintype "passive+no_connect"))
    )
    (net (code "53") (name "unconnected-(J800-D--Pad2)") (class "Default")
      (node (ref "J800") (pin "2") (pinfunction "D-_2") (pintype "passive+no_connect"))
    )
    (net (code "54") (name "unconnected-(J800-ID-Pad4)") (class "Default")
      (node (ref "J800") (pin "4") (pinfunction "ID_4") (pintype "passive+no_connect"))
    )
    (net (code "55") (name "unconnected-(J800-Shield-PadS)") (class "Default")
      (node (ref "J800") (pin "S") (pinfunction "Shield_S") (pintype "passive+no_connect"))
    )
    (net (code "56") (name "unconnected-(U802-PG-Pad7)") (class "Default")
      (node (ref "U802") (pin "7") (pinfunction "PG_7") (pintype "passive+no_connect"))
    )
  )
)
